# gydrodrive_rs485.net
KiCad netlist of a schematic drawn in Altium Designer
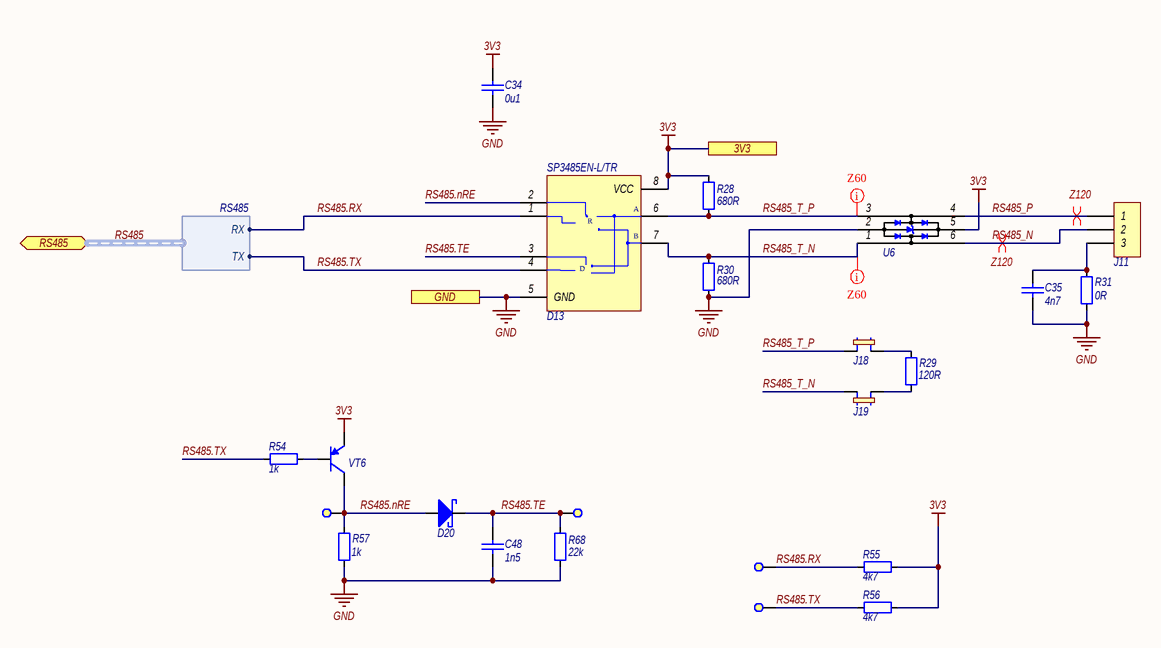
[diagram p0: gydrodrive_rs485.SchDoc]

(export (version "E")
  (design (tool "Eeschema 10.0.6"))
  (components
    (comp (ref "C34")
      (value "CAP_0805")
      (footprint "CAPC2012-0805M")
      (description "Конденсатор керамический, корпус 0805")
      (fields
        (field (name "CAPACITANCE") "0u1")
        (field (name "PART NUMBER") "CAPC_0805")
        (field (name "VOLTAGE") "50V")
      )
      (libsource (lib "StdLib") (part "CAP"))
    )
    (comp (ref "C35")
      (value "CAP_1206")
      (footprint "CAPC3216-1206M")
      (description "Конденсатор керамический, корпус 1206")
      (fields
        (field (name "CAPACITANCE") "4n7")
        (field (name "PART NUMBER") "CAPC_1206")
        (field (name "VOLTAGE") "50V")
      )
      (libsource (lib "StdLib") (part "CAP"))
    )
    (comp (ref "C48")
      (value "CAP_0805")
      (footprint "CAPC2012-0805M")
      (description "Конденсатор керамический, корпус 0805")
      (fields
        (field (name "CAPACITANCE") "1n5")
        (field (name "PART NUMBER") "CAPC_0805")
        (field (name "VOLTAGE") "50V")
      )
      (libsource (lib "StdLib") (part "CAP"))
    )
    (comp (ref "D13")
      (value "SP3485EN-L/TR")
      (footprint "SO8_M")
      (description "Дифференциальный приемопередатчик rs485")
      (libsource (lib "StdLib") (part "RS485_SO8"))
    )
    (comp (ref "D20")
      (value "MBR0540")
      (footprint "SOD_123_M")
      (description "Диод Шоттки")
      (fields (field (name "VOLTAGE") "40V"))
      (libsource (lib "StdLib") (part "SCHOTTKY"))
    )
    (comp (ref "J11")
      (value "DG142V-5.08-03P")
      (footprint "DG142V-5.08-03P")
      (description "Клеммник 3-контактный, шаг 5.08 мм")
      (libsource (lib "StdLib") (part "PIN1x3"))
    )
    (comp (ref "J18")
      (value "PLS-2.54-2 JUMP")
      (footprint "PLS-2-2.54")
      (description "Разъем штыревой шаг 2.54 мм")
      (libsource (lib "StdLib") (part "PIN1x2_JUMP"))
    )
    (comp (ref "J19")
      (value "PLS-2.54-2 JUMP")
      (footprint "PLS-2-2.54")
      (description "Разъем штыревой шаг 2.54 мм")
      (libsource (lib "") (part "PIN1x2_JUMP_1"))
    )
    (comp (ref "R28")
      (value "RES_1206")
      (footprint "RESC3216-1206M")
      (description "Рез-р, корпус 1206")
      (fields
        (field (name "RESISTANCE") "680R")
        (field (name "PART NUMBER") "RESC_1206")
        (field (name "TOLERANCE") "5%")
      )
      (libsource (lib "") (part "RES_1"))
    )
    (comp (ref "R29")
      (value "RES_1206")
      (footprint "RESC3216-1206M")
      (description "Рез-р, корпус 1206")
      (fields
        (field (name "RESISTANCE") "120R")
        (field (name "PART NUMBER") "RESC_1206")
        (field (name "TOLERANCE") "5%")
      )
      (libsource (lib "") (part "RES_1"))
    )
    (comp (ref "R30")
      (value "RES_1206")
      (footprint "RESC3216-1206M")
      (description "Рез-р, корпус 1206")
      (fields
        (field (name "RESISTANCE") "680R")
        (field (name "PART NUMBER") "RESC_1206")
        (field (name "TOLERANCE") "5%")
      )
      (libsource (lib "") (part "RES_1"))
    )
    (comp (ref "R31")
      (value "RES_1206")
      (footprint "RESC3216-1206M")
      (description "Рез-р, корпус 1206")
      (fields
        (field (name "RESISTANCE") "0R")
        (field (name "PART NUMBER") "RESC_1206")
        (field (name "TOLERANCE") "5%")
      )
      (libsource (lib "") (part "RES_2"))
    )
    (comp (ref "R54")
      (value "RES_0805")
      (footprint "RESC2012-0805M")
      (description "Рез-р, корпус 0805")
      (fields
        (field (name "RESISTANCE") "1k")
        (field (name "PART NUMBER") "RESC_0805")
        (field (name "TOLERANCE") "5%")
      )
      (libsource (lib "StdLib") (part "RES"))
    )
    (comp (ref "R55")
      (value "RES_0805")
      (footprint "RESC2012-0805M")
      (description "Рез-р, корпус 0805")
      (fields
        (field (name "RESISTANCE") "4k7")
        (field (name "PART NUMBER") "RESC_0805")
        (field (name "TOLERANCE") "5%")
      )
      (libsource (lib "StdLib") (part "RES"))
    )
    (comp (ref "R56")
      (value "RES_0805")
      (footprint "RESC2012-0805M")
      (description "Рез-р, корпус 0805")
      (fields
        (field (name "RESISTANCE") "4k7")
        (field (name "PART NUMBER") "RESC_0805")
        (field (name "TOLERANCE") "5%")
      )
      (libsource (lib "StdLib") (part "RES"))
    )
    (comp (ref "R57")
      (value "RES_0805")
      (footprint "RESC2012-0805M")
      (description "Рез-р, корпус 0805")
      (fields
        (field (name "RESISTANCE") "1k")
        (field (name "PART NUMBER") "RESC_0805")
        (field (name "TOLERANCE") "5%")
      )
      (libsource (lib "") (part "RES_1"))
    )
    (comp (ref "R68")
      (value "RES_0805")
      (footprint "RESC2012-0805M")
      (description "Рез-р, корпус 0805")
      (fields
        (field (name "RESISTANCE") "22k")
        (field (name "PART NUMBER") "RESC_0805")
        (field (name "TOLERANCE") "5%")
      )
      (libsource (lib "") (part "RES_1"))
    )
    (comp (ref "TP1")
      (value "Test point 1")
      (footprint "TP_1")
      (description "Тестовый контакт круглый 1 мм")
      (libsource (lib "StdLib") (part "Test point"))
    )
    (comp (ref "TP10")
      (value "Test point 1")
      (footprint "TP_1")
      (description "Тестовый контакт круглый 1 мм")
      (libsource (lib "StdLib") (part "Test point"))
    )
    (comp (ref "TP11")
      (value "Test point 1")
      (footprint "TP_1")
      (description "Тестовый контакт круглый 1 мм")
      (libsource (lib "StdLib") (part "Test point"))
    )
    (comp (ref "TP19")
      (value "Test point 1")
      (footprint "TP_1")
      (description "Тестовый контакт круглый 1 мм")
      (libsource (lib "StdLib") (part "Test point"))
    )
    (comp (ref "U6")
      (value "USBLC6-2SC6")
      (footprint "SOT23-6AM")
      (description "Диодная сборка для защиты дифференциальной линии")
      (fields (field (name "VOLTAGE") "5.25V"))
      (libsource (lib "StdLib") (part "USBLC6-2SC6"))
    )
    (comp (ref "VT6")
      (value "BC807")
      (footprint "SOT23-3M")
      (description "Биполярный транзистор")
      (fields (field (name "VOLTAGE") "45V"))
      (libsource (lib "StdLib") (part "BJT_PNP_SOT23"))
    )
  )
  (nets
    (net (code "2") (name "/RS485.RX") (class "Default")
      (node (ref "D13") (pin "1") (pinfunction "RO_1") (pintype "passive"))
      (node (ref "R55") (pin "2") (pinfunction "2_2") (pintype "passive"))
      (node (ref "TP10") (pin "1") (pinfunction "1_1") (pintype "passive"))
    )
    (net (code "3") (name "/RS485.TE") (class "Default")
      (node (ref "C48") (pin "2") (pinfunction "2_2") (pintype "passive"))
      (node (ref "D13") (pin "3") (pinfunction "DE_3") (pintype "passive"))
      (node (ref "D20") (pin "1") (pinfunction "K_1") (pintype "passive"))
      (node (ref "R68") (pin "2") (pinfunction "2_2") (pintype "passive"))
      (node (ref "TP11") (pin "1") (pinfunction "1_1") (pintype "passive"))
    )
    (net (code "4") (name "/RS485.TX") (class "Default")
      (node (ref "D13") (pin "4") (pinfunction "DI_4") (pintype "passive"))
      (node (ref "R54") (pin "2") (pinfunction "2_2") (pintype "passive"))
      (node (ref "R56") (pin "2") (pinfunction "2_2") (pintype "passive"))
      (node (ref "TP1") (pin "1") (pinfunction "1_1") (pintype "passive"))
    )
    (net (code "5") (name "/RS485.nRE") (class "Default")
      (node (ref "D13") (pin "2") (pinfunction "~{RE}_2") (pintype "passive"))
      (node (ref "D20") (pin "2") (pinfunction "A_2") (pintype "passive"))
      (node (ref "R57") (pin "2") (pinfunction "2_2") (pintype "passive"))
      (node (ref "TP19") (pin "1") (pinfunction "1_1") (pintype "passive"))
      (node (ref "VT6") (pin "3") (pinfunction "C_3") (pintype "passive"))
    )
    (net (code "6") (name "/RS485_N") (class "Default")
      (node (ref "J11") (pin "2") (pinfunction "2_2") (pintype "passive"))
      (node (ref "U6") (pin "6") (pinfunction "IO1_6") (pintype "passive"))
    )
    (net (code "7") (name "/RS485_P") (class "Default")
      (node (ref "J11") (pin "1") (pinfunction "1_1") (pintype "passive"))
      (node (ref "U6") (pin "4") (pinfunction "IO2_4") (pintype "passive"))
    )
    (net (code "8") (name "/RS485_T_N") (class "Default")
      (node (ref "D13") (pin "7") (pinfunction "B_7") (pintype "passive"))
      (node (ref "J19") (pin "2") (pinfunction "2_2") (pintype "passive"))
      (node (ref "R30") (pin "2") (pinfunction "2_2") (pintype "passive"))
      (node (ref "U6") (pin "1") (pinfunction "IO1_1") (pintype "passive"))
    )
    (net (code "9") (name "/RS485_T_P") (class "Default")
      (node (ref "D13") (pin "6") (pinfunction "A_6") (pintype "passive"))
      (node (ref "J18") (pin "2") (pinfunction "2_2") (pintype "passive"))
      (node (ref "R28") (pin "1") (pinfunction "1_1") (pintype "passive"))
      (node (ref "U6") (pin "3") (pinfunction "IO2_3") (pintype "passive"))
    )
    (net (code "11") (name "3V3") (class "Default")
      (node (ref "C34") (pin "2") (pinfunction "2_2") (pintype "passive"))
      (node (ref "D13") (pin "8") (pinfunction "VCC_8") (pintype "passive"))
      (node (ref "R28") (pin "2") (pinfunction "2_2") (pintype "passive"))
      (node (ref "R55") (pin "1") (pinfunction "1_1") (pintype "passive"))
      (node (ref "R56") (pin "1") (pinfunction "1_1") (pintype "passive"))
      (node (ref "U6") (pin "5") (pinfunction "Vbus_5") (pintype "passive"))
      (node (ref "VT6") (pin "2") (pinfunction "E_2") (pintype "passive"))
    )
    (net (code "12") (name "GND") (class "Default")
      (node (ref "C34") (pin "1") (pinfunction "1_1") (pintype "passive"))
      (node (ref "C35") (pin "1") (pinfunction "1_1") (pintype "passive"))
      (node (ref "C48") (pin "1") (pinfunction "1_1") (pintype "passive"))
      (node (ref "D13") (pin "5") (pinfunction "GND_5") (pintype "passive"))
      (node (ref "R30") (pin "1") (pinfunction "1_1") (pintype "passive"))
      (node (ref "R31") (pin "2") (pinfunction "2_2") (pintype "passive"))
      (node (ref "R57") (pin "1") (pinfunction "1_1") (pintype "passive"))
      (node (ref "R68") (pin "1") (pinfunction "1_1") (pintype "passive"))
      (node (ref "U6") (pin "2") (pinfunction "GND_2") (pintype "passive"))
    )
    (net (code "13") (name "Net-(C35-Pad2)") (class "Default")
      (node (ref "C35") (pin "2") (pinfunction "2_2") (pintype "passive"))
      (node (ref "J11") (pin "3") (pinfunction "3_3") (pintype "passive"))
      (node (ref "R31") (pin "1") (pinfunction "1_1") (pintype "passive"))
    )
    (net (code "14") (name "Net-(J18-Pad1)") (class "Default")
      (node (ref "J18") (pin "1") (pinfunction "1_1") (pintype "passive"))
      (node (ref "R29") (pin "2") (pinfunction "2_2") (pintype "passive"))
    )
    (net (code "15") (name "Net-(J19-Pad1)") (class "Default")
      (node (ref "J19") (pin "1") (pinfunction "1_1") (pintype "passive"))
      (node (ref "R29") (pin "1") (pinfunction "1_1") (pintype "passive"))
    )
    (net (code "16") (name "Net-(VT6-B)") (class "Default")
      (node (ref "R54") (pin "1") (pinfunction "1_1") (pintype "passive"))
      (node (ref "VT6") (pin "1") (pinfunction "B_1") (pintype "passive"))
    )
  )
)
